# MCU.net
KiCad netlist of a schematic drawn in Altium Designer
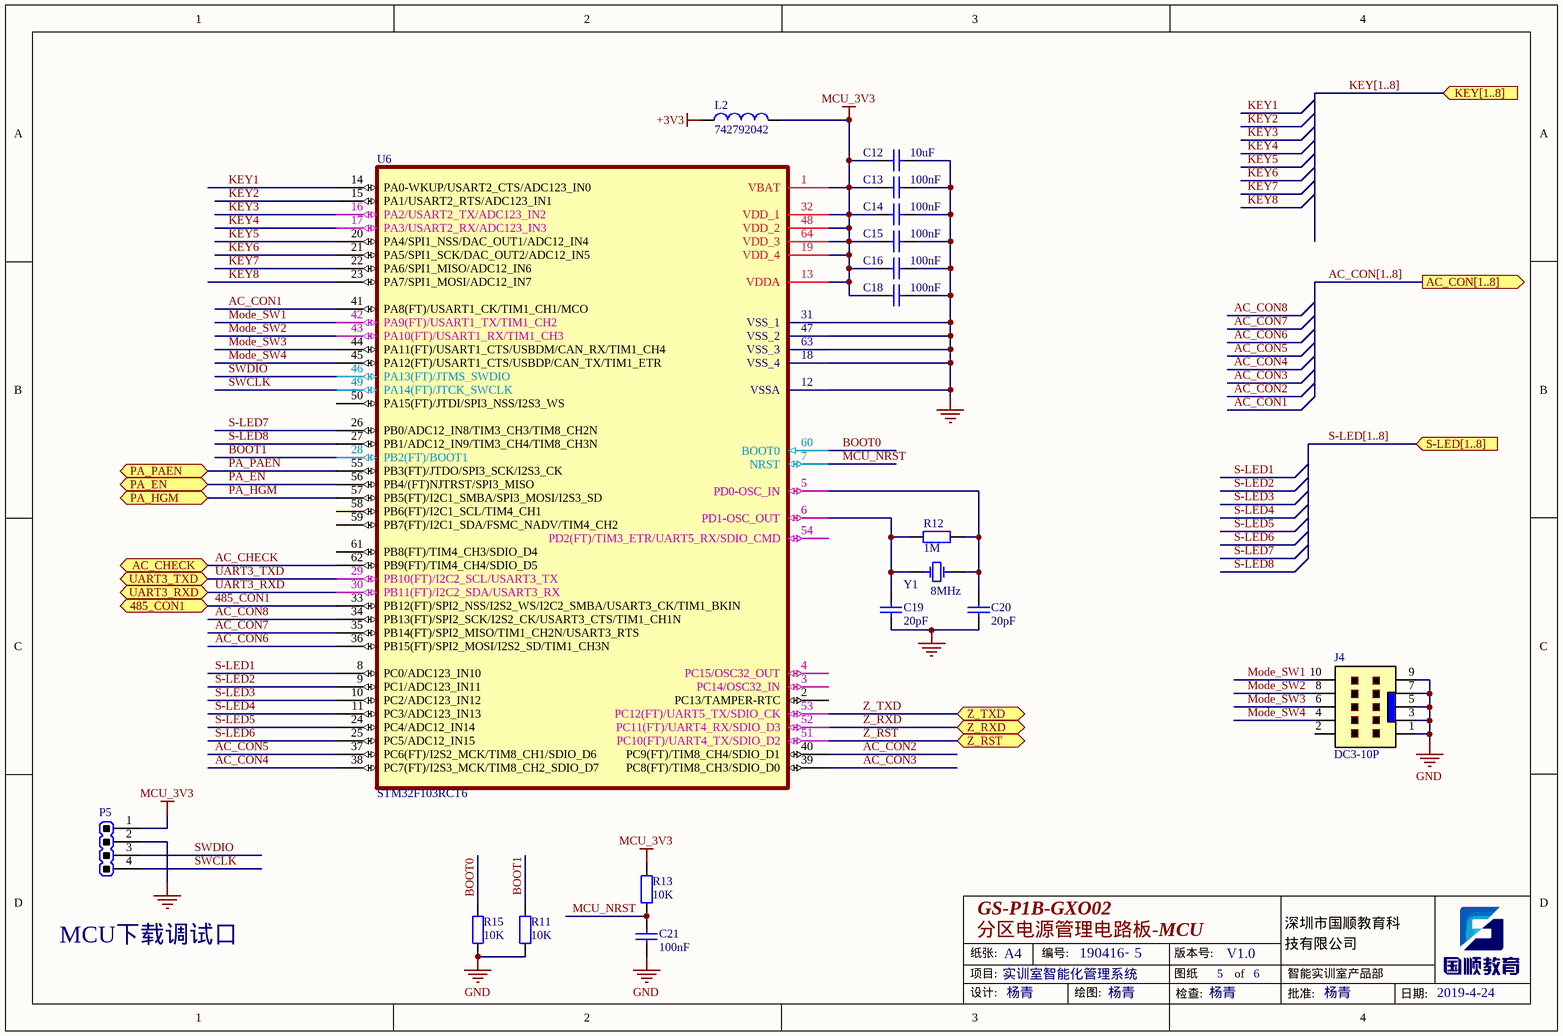
[diagram p0: MCU.SchDoc]

(export (version "E")
  (design (tool "Eeschema 10.0.6"))
  (components
    (comp (ref "C12")
      (value "10uF")
      (footprint "C0603")
      (description "Capacitor")
      (libsource (lib "贴片电容") (part "10uF_16V_0603"))
    )
    (comp (ref "C13")
      (value "100nF")
      (footprint "C0603")
      (description "Capacitor")
      (libsource (lib "贴片电容") (part "100nF_50V_0603"))
    )
    (comp (ref "C14")
      (value "100nF")
      (footprint "C0603")
      (description "Capacitor")
      (libsource (lib "贴片电容") (part "100nF_50V_0603"))
    )
    (comp (ref "C15")
      (value "100nF")
      (footprint "C0603")
      (description "Capacitor")
      (libsource (lib "贴片电容") (part "100nF_50V_0603"))
    )
    (comp (ref "C16")
      (value "100nF")
      (footprint "C0603")
      (description "Capacitor")
      (libsource (lib "贴片电容") (part "100nF_50V_0603"))
    )
    (comp (ref "C18")
      (value "100nF")
      (footprint "C0603")
      (description "Capacitor")
      (libsource (lib "贴片电容") (part "100nF_50V_0603"))
    )
    (comp (ref "C19")
      (value "20pF")
      (footprint "C0603")
      (description "Capacitor")
      (libsource (lib "贴片电容") (part "20pF_50V_0603"))
    )
    (comp (ref "C20")
      (value "20pF")
      (footprint "C0603")
      (description "Capacitor")
      (libsource (lib "贴片电容") (part "20pF_50V_0603"))
    )
    (comp (ref "C21")
      (value "100nF")
      (footprint "C0603")
      (description "Capacitor")
      (libsource (lib "贴片电容") (part "100nF_50V_0603"))
    )
    (comp (ref "J4") (value "DC3-10P") (footprint "DC3-2*5-2.54-M") (libsource (lib "连接器") (part "DC3-10P")))
    (comp (ref "L2")
      (value "742792042")
      (footprint "L0805")
      (description "磁珠,WE-CBF,600@100M,\r\n500Ohm,200mA,0805,742792042")
      (libsource (lib "电感") (part "BEAD-742792042_0805"))
    )
    (comp (ref "P5")
      (value "HDRM-2.54/11-1*4P-AK")
      (footprint "HDRM-2.54-1*4P-AK1")
      (description "排针,直")
      (libsource (lib "连接器") (part "HDRM-2.54/11-1*4P-AK"))
    )
    (comp (ref "R11")
      (value "10K")
      (footprint "R0603")
      (description "10K,±5%,0603")
      (libsource (lib "贴片电阻") (part "10K_5%_0603"))
    )
    (comp (ref "R12")
      (value "1M")
      (footprint "R0603")
      (description "1M,±5%,0603")
      (libsource (lib "贴片电阻") (part "1M_5%_0603"))
    )
    (comp (ref "R13")
      (value "10K")
      (footprint "R0603")
      (description "10K,±5%,0603")
      (libsource (lib "贴片电阻") (part "10K_5%_0603"))
    )
    (comp (ref "R15")
      (value "10K")
      (footprint "R0603")
      (description "10K,±5%,0603")
      (libsource (lib "贴片电阻") (part "10K_5%_0603"))
    )
    (comp (ref "U6")
      (value "STM32F103RCT6")
      (footprint "LQFP64")
      (libsource (lib "IC") (part "STM32F103RCT6-LQFP64_1"))
    )
    (comp (ref "Y1")
      (value "8MHz")
      (footprint "X_HC49-S")
      (description "8MHz,HC-49S")
      (libsource (lib "杂项元件") (part "CRYSTAL_8M_HC49S"))
    )
  )
  (nets
    (net (code "1") (name "+3V3") (class "Default")
      (node (ref "L2") (pin "2") (pinfunction "2_2") (pintype "passive"))
    )
    (net (code "2") (name "/485_CON1") (class "Default")
      (node (ref "U6") (pin "33") (pinfunction "PB12(FT)/SPI2_NSS/I2S2_WS/I2C2_SMBA/USART3_CK/TIM1_BKIN_33") (pintype "bidirectional"))
    )
    (net (code "3") (name "/AC_CHECK") (class "Default")
      (node (ref "U6") (pin "62") (pinfunction "PB9(FT)/TIM4_CH4/SDIO_D5_62") (pintype "bidirectional"))
    )
    (net (code "4") (name "/AC_CON1") (class "Default")
      (node (ref "U6") (pin "41") (pinfunction "PA8(FT)/USART1_CK/TIM1_CH1/MCO_41") (pintype "bidirectional"))
    )
    (net (code "5") (name "/AC_CON2") (class "Default")
      (node (ref "U6") (pin "40") (pinfunction "PC9(FT)/TIM8_CH4/SDIO_D1_40") (pintype "bidirectional"))
    )
    (net (code "6") (name "/AC_CON3") (class "Default")
      (node (ref "U6") (pin "39") (pinfunction "PC8(FT)/TIM8_CH3/SDIO_D0_39") (pintype "bidirectional"))
    )
    (net (code "7") (name "/AC_CON4") (class "Default")
      (node (ref "U6") (pin "38") (pinfunction "PC7(FT)/I2S3_MCK/TIM8_CH2_SDIO_D7_38") (pintype "bidirectional"))
    )
    (net (code "8") (name "/AC_CON5") (class "Default")
      (node (ref "U6") (pin "37") (pinfunction "PC6(FT)/I2S2_MCK/TIM8_CH1/SDIO_D6_37") (pintype "bidirectional"))
    )
    (net (code "9") (name "/AC_CON6") (class "Default")
      (node (ref "U6") (pin "36") (pinfunction "PB15(FT)/SPI2_MOSI/I2S2_SD/TIM1_CH3N_36") (pintype "bidirectional"))
    )
    (net (code "10") (name "/AC_CON7") (class "Default")
      (node (ref "U6") (pin "35") (pinfunction "PB14(FT)/SPI2_MISO/TIM1_CH2N/USART3_RTS_35") (pintype "bidirectional"))
    )
    (net (code "11") (name "/AC_CON8") (class "Default")
      (node (ref "U6") (pin "34") (pinfunction "PB13(FT)/SPI2_SCK/I2S2_CK/USART3_CTS/TIM1_CH1N_34") (pintype "bidirectional"))
    )
    (net (code "13") (name "/BOOT0") (class "Default")
      (node (ref "R15") (pin "2") (pinfunction "2_2") (pintype "passive"))
      (node (ref "U6") (pin "60") (pinfunction "BOOT0_60") (pintype "input"))
    )
    (net (code "14") (name "/BOOT1") (class "Default")
      (node (ref "R11") (pin "2") (pinfunction "2_2") (pintype "passive"))
      (node (ref "U6") (pin "28") (pinfunction "PB2(FT)/BOOT1_28") (pintype "bidirectional"))
    )
    (net (code "15") (name "/KEY1") (class "Default")
      (node (ref "U6") (pin "14") (pinfunction "PA0-WKUP/USART2_CTS/ADC123_IN0_14") (pintype "bidirectional"))
    )
    (net (code "16") (name "/KEY2") (class "Default")
      (node (ref "U6") (pin "15") (pinfunction "PA1/USART2_RTS/ADC123_IN1_15") (pintype "bidirectional"))
    )
    (net (code "17") (name "/KEY3") (class "Default")
      (node (ref "U6") (pin "16") (pinfunction "PA2/USART2_TX/ADC123_IN2_16") (pintype "bidirectional"))
    )
    (net (code "18") (name "/KEY4") (class "Default")
      (node (ref "U6") (pin "17") (pinfunction "PA3/USART2_RX/ADC123_IN3_17") (pintype "bidirectional"))
    )
    (net (code "19") (name "/KEY5") (class "Default")
      (node (ref "U6") (pin "20") (pinfunction "PA4/SPI1_NSS/DAC_OUT1/ADC12_IN4_20") (pintype "bidirectional"))
    )
    (net (code "20") (name "/KEY6") (class "Default")
      (node (ref "U6") (pin "21") (pinfunction "PA5/SPI1_SCK/DAC_OUT2/ADC12_IN5_21") (pintype "bidirectional"))
    )
    (net (code "21") (name "/KEY7") (class "Default")
      (node (ref "U6") (pin "22") (pinfunction "PA6/SPI1_MISO/ADC12_IN6_22") (pintype "bidirectional"))
    )
    (net (code "22") (name "/KEY8") (class "Default")
      (node (ref "U6") (pin "23") (pinfunction "PA7/SPI1_MOSI/ADC12_IN7_23") (pintype "bidirectional"))
    )
    (net (code "24") (name "/MCU_NRST") (class "Default")
      (node (ref "C21") (pin "1") (pinfunction "1_1") (pintype "passive"))
      (node (ref "R13") (pin "1") (pinfunction "1_1") (pintype "passive"))
      (node (ref "U6") (pin "7") (pinfunction "NRST_7") (pintype "bidirectional"))
    )
    (net (code "25") (name "/Mode_SW1") (class "Default")
      (node (ref "J4") (pin "10") (pinfunction "10_10") (pintype "passive"))
      (node (ref "U6") (pin "42") (pinfunction "PA9(FT)/USART1_TX/TIM1_CH2_42") (pintype "bidirectional"))
    )
    (net (code "26") (name "/Mode_SW2") (class "Default")
      (node (ref "J4") (pin "8") (pinfunction "8_8") (pintype "passive"))
      (node (ref "U6") (pin "43") (pinfunction "PA10(FT)/USART1_RX/TIM1_CH3_43") (pintype "bidirectional"))
    )
    (net (code "27") (name "/Mode_SW3") (class "Default")
      (node (ref "J4") (pin "6") (pinfunction "6_6") (pintype "passive"))
      (node (ref "U6") (pin "44") (pinfunction "PA11(FT)/USART1_CTS/USBDM/CAN_RX/TIM1_CH4_44") (pintype "bidirectional"))
    )
    (net (code "28") (name "/Mode_SW4") (class "Default")
      (node (ref "J4") (pin "4") (pinfunction "4_4") (pintype "passive"))
      (node (ref "U6") (pin "45") (pinfunction "PA12(FT)/USART1_CTS/USBDP/CAN_TX/TIM1_ETR_45") (pintype "bidirectional"))
    )
    (net (code "29") (name "/PA_EN") (class "Default")
      (node (ref "U6") (pin "56") (pinfunction "PB4/(FT)NJTRST/SPI3_MISO_56") (pintype "bidirectional"))
    )
    (net (code "30") (name "/PA_HGM") (class "Default")
      (node (ref "U6") (pin "57") (pinfunction "PB5(FT)/I2C1_SMBA/SPI3_MOSI/I2S3_SD_57") (pintype "bidirectional"))
    )
    (net (code "31") (name "/PA_PAEN") (class "Default")
      (node (ref "U6") (pin "55") (pinfunction "PB3(FT)/JTDO/SPI3_SCK/I2S3_CK_55") (pintype "bidirectional"))
    )
    (net (code "32") (name "/S-LED1") (class "Default")
      (node (ref "U6") (pin "8") (pinfunction "PC0/ADC123_IN10_8") (pintype "bidirectional"))
    )
    (net (code "33") (name "/S-LED2") (class "Default")
      (node (ref "U6") (pin "9") (pinfunction "PC1/ADC123_IN11_9") (pintype "bidirectional"))
    )
    (net (code "34") (name "/S-LED3") (class "Default")
      (node (ref "U6") (pin "10") (pinfunction "PC2/ADC123_IN12_10") (pintype "bidirectional"))
    )
    (net (code "35") (name "/S-LED4") (class "Default")
      (node (ref "U6") (pin "11") (pinfunction "PC3/ADC123_IN13_11") (pintype "bidirectional"))
    )
    (net (code "36") (name "/S-LED5") (class "Default")
      (node (ref "U6") (pin "24") (pinfunction "PC4/ADC12_IN14_24") (pintype "bidirectional"))
    )
    (net (code "37") (name "/S-LED6") (class "Default")
      (node (ref "U6") (pin "25") (pinfunction "PC5/ADC12_IN15_25") (pintype "bidirectional"))
    )
    (net (code "38") (name "/S-LED7") (class "Default")
      (node (ref "U6") (pin "26") (pinfunction "PB0/ADC12_IN8/TIM3_CH3/TIM8_CH2N_26") (pintype "bidirectional"))
    )
    (net (code "39") (name "/S-LED8") (class "Default")
      (node (ref "U6") (pin "27") (pinfunction "PB1/ADC12_IN9/TIM3_CH4/TIM8_CH3N_27") (pintype "bidirectional"))
    )
    (net (code "41") (name "/SWCLK") (class "Default")
      (node (ref "P5") (pin "4") (pinfunction "4_4") (pintype "passive"))
      (node (ref "U6") (pin "49") (pinfunction "PA14(FT)/JTCK_SWCLK_49") (pintype "bidirectional"))
    )
    (net (code "42") (name "/SWDIO") (class "Default")
      (node (ref "P5") (pin "3") (pinfunction "3_3") (pintype "passive"))
      (node (ref "U6") (pin "46") (pinfunction "PA13(FT)/JTMS_SWDIO_46") (pintype "bidirectional"))
    )
    (net (code "43") (name "/UART3_RXD") (class "Default")
      (node (ref "U6") (pin "30") (pinfunction "PB11(FT)/I2C2_SDA/USART3_RX_30") (pintype "bidirectional"))
    )
    (net (code "44") (name "/UART3_TXD") (class "Default")
      (node (ref "U6") (pin "29") (pinfunction "PB10(FT)/I2C2_SCL/USART3_TX_29") (pintype "bidirectional"))
    )
    (net (code "45") (name "/Z_RST") (class "Default")
      (node (ref "U6") (pin "51") (pinfunction "PC10(FT)/UART4_TX/SDIO_D2_51") (pintype "bidirectional"))
    )
    (net (code "46") (name "/Z_RXD") (class "Default")
      (node (ref "U6") (pin "52") (pinfunction "PC11(FT)/UART4_RX/SDIO_D3_52") (pintype "bidirectional"))
    )
    (net (code "47") (name "/Z_TXD") (class "Default")
      (node (ref "U6") (pin "53") (pinfunction "PC12(FT)/UART5_TX/SDIO_CK_53") (pintype "bidirectional"))
    )
    (net (code "48") (name "GND") (class "Default")
      (node (ref "C12") (pin "1") (pinfunction "1_1") (pintype "passive"))
      (node (ref "C13") (pin "2") (pinfunction "2_2") (pintype "passive"))
      (node (ref "C14") (pin "2") (pinfunction "2_2") (pintype "passive"))
      (node (ref "C15") (pin "1") (pinfunction "1_1") (pintype "passive"))
      (node (ref "C16") (pin "1") (pinfunction "1_1") (pintype "passive"))
      (node (ref "C18") (pin "2") (pinfunction "2_2") (pintype "passive"))
      (node (ref "C19") (pin "2") (pinfunction "2_2") (pintype "passive"))
      (node (ref "C20") (pin "2") (pinfunction "2_2") (pintype "passive"))
      (node (ref "C21") (pin "2") (pinfunction "2_2") (pintype "passive"))
      (node (ref "J4") (pin "1") (pinfunction "1_1") (pintype "passive"))
      (node (ref "J4") (pin "3") (pinfunction "3_3") (pintype "passive"))
      (node (ref "J4") (pin "5") (pinfunction "5_5") (pintype "passive"))
      (node (ref "J4") (pin "7") (pinfunction "7_7") (pintype "passive"))
      (node (ref "J4") (pin "9") (pinfunction "9_9") (pintype "passive"))
      (node (ref "P5") (pin "2") (pinfunction "2_2") (pintype "passive"))
      (node (ref "R11") (pin "1") (pinfunction "1_1") (pintype "passive"))
      (node (ref "R15") (pin "1") (pinfunction "1_1") (pintype "passive"))
      (node (ref "U6") (pin "12") (pinfunction "VSSA_12") (pintype "power_in"))
      (node (ref "U6") (pin "18") (pinfunction "VSS_4_18") (pintype "power_in"))
      (node (ref "U6") (pin "31") (pinfunction "VSS_1_31") (pintype "power_in"))
      (node (ref "U6") (pin "47") (pinfunction "VSS_2_47") (pintype "power_in"))
      (node (ref "U6") (pin "63") (pinfunction "VSS_3_63") (pintype "power_in"))
    )
    (net (code "49") (name "MCU_3V3") (class "Default")
      (node (ref "C12") (pin "2") (pinfunction "2_2") (pintype "passive"))
      (node (ref "C13") (pin "1") (pinfunction "1_1") (pintype "passive"))
      (node (ref "C14") (pin "1") (pinfunction "1_1") (pintype "passive"))
      (node (ref "C15") (pin "2") (pinfunction "2_2") (pintype "passive"))
      (node (ref "C16") (pin "2") (pinfunction "2_2") (pintype "passive"))
      (node (ref "C18") (pin "1") (pinfunction "1_1") (pintype "passive"))
      (node (ref "L2") (pin "1") (pinfunction "1_1") (pintype "passive"))
      (node (ref "P5") (pin "1") (pinfunction "1_1") (pintype "passive"))
      (node (ref "R13") (pin "2") (pinfunction "2_2") (pintype "passive"))
      (node (ref "U6") (pin "1") (pinfunction "VBAT_1") (pintype "power_in"))
      (node (ref "U6") (pin "13") (pinfunction "VDDA_13") (pintype "power_in"))
      (node (ref "U6") (pin "19") (pinfunction "VDD_4_19") (pintype "power_in"))
      (node (ref "U6") (pin "32") (pinfunction "VDD_1_32") (pintype "power_in"))
      (node (ref "U6") (pin "48") (pinfunction "VDD_2_48") (pintype "power_in"))
      (node (ref "U6") (pin "64") (pinfunction "VDD_3_64") (pintype "power_in"))
    )
    (net (code "50") (name "Net-(U6-PD0-OSC_IN)") (class "Default")
      (node (ref "C20") (pin "1") (pinfunction "1_1") (pintype "passive"))
      (node (ref "R12") (pin "2") (pinfunction "2_2") (pintype "passive"))
      (node (ref "U6") (pin "5") (pinfunction "PD0-OSC_IN_5") (pintype "bidirectional"))
      (node (ref "Y1") (pin "2") (pinfunction "2_2") (pintype "passive"))
    )
    (net (code "51") (name "Net-(U6-PD1-OSC_OUT)") (class "Default")
      (node (ref "C19") (pin "1") (pinfunction "1_1") (pintype "passive"))
      (node (ref "R12") (pin "1") (pinfunction "1_1") (pintype "passive"))
      (node (ref "U6") (pin "6") (pinfunction "PD1-OSC_OUT_6") (pintype "bidirectional"))
      (node (ref "Y1") (pin "1") (pinfunction "1_1") (pintype "passive"))
    )
    (net (code "52") (name "unconnected-(J4-Pad2)") (class "Default")
      (node (ref "J4") (pin "2") (pinfunction "2_2") (pintype "passive"))
    )
    (net (code "53") (name "unconnected-(U6-PA15(FT){slash}JTDI{slash}SPI3_NSS{slash}I2S3_WS-Pad50)") (class "Default")
      (node (ref "U6") (pin "50") (pinfunction "PA15(FT)/JTDI/SPI3_NSS/I2S3_WS_50") (pintype "bidirectional"))
    )
    (net (code "54") (name "unconnected-(U6-PB6(FT){slash}I2C1_SCL{slash}TIM4_CH1-Pad58)") (class "Default")
      (node (ref "U6") (pin "58") (pinfunction "PB6(FT)/I2C1_SCL/TIM4_CH1_58") (pintype "bidirectional"))
    )
    (net (code "55") (name "unconnected-(U6-PB7(FT){slash}I2C1_SDA{slash}FSMC_NADV{slash}TIM4_CH2-Pad59)") (class "Default")
      (node (ref "U6") (pin "59") (pinfunction "PB7(FT)/I2C1_SDA/FSMC_NADV/TIM4_CH2_59") (pintype "bidirectional"))
    )
    (net (code "56") (name "unconnected-(U6-PB8(FT){slash}TIM4_CH3{slash}SDIO_D4-Pad61)") (class "Default")
      (node (ref "U6") (pin "61") (pinfunction "PB8(FT)/TIM4_CH3/SDIO_D4_61") (pintype "bidirectional"))
    )
    (net (code "57") (name "unconnected-(U6-PC13{slash}TAMPER-RTC-Pad2)") (class "Default")
      (node (ref "U6") (pin "2") (pinfunction "PC13/TAMPER-RTC_2") (pintype "bidirectional"))
    )
    (net (code "58") (name "unconnected-(U6-PC14{slash}OSC32_IN-Pad3)") (class "Default")
      (node (ref "U6") (pin "3") (pinfunction "PC14/OSC32_IN_3") (pintype "bidirectional"))
    )
    (net (code "59") (name "unconnected-(U6-PC15{slash}OSC32_OUT-Pad4)") (class "Default")
      (node (ref "U6") (pin "4") (pinfunction "PC15/OSC32_OUT_4") (pintype "bidirectional"))
    )
    (net (code "60") (name "unconnected-(U6-PD2(FT){slash}TIM3_ETR{slash}UART5_RX{slash}SDIO_CMD-Pad54)") (class "Default")
      (node (ref "U6") (pin "54") (pinfunction "PD2(FT)/TIM3_ETR/UART5_RX/SDIO_CMD_54") (pintype "bidirectional"))
    )
  )
)
